# automotive-microcontroller-small-junctio.net
KiCad netlist of a schematic drawn in Altium Designer
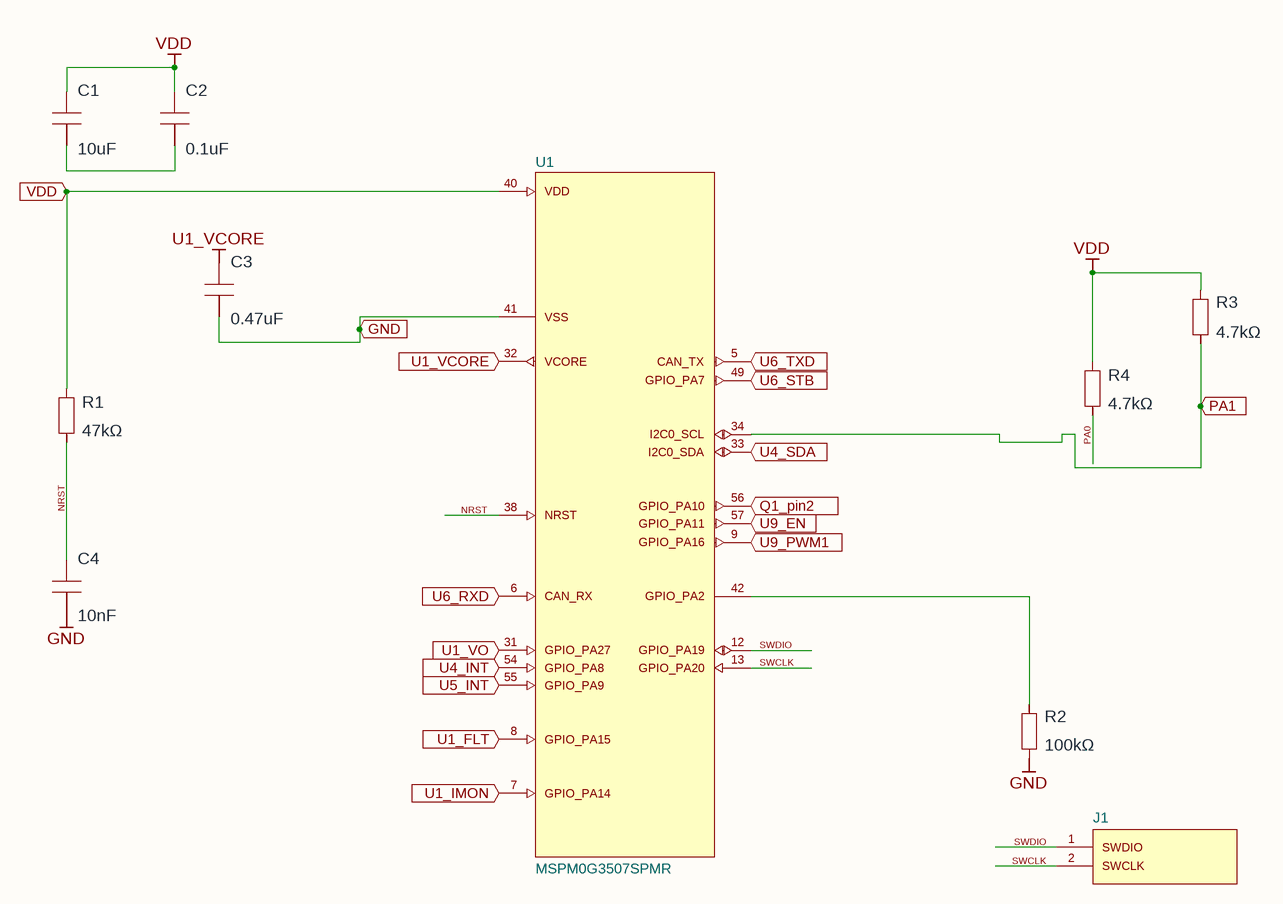
[diagram p0: automotive-microcontroller-small-junctions.SchDoc]

(export (version "E")
  (design (tool "Eeschema 10.0.6"))
  (components
    (comp (ref "C1") (value "10uF") (libsource (lib "altium-import") (part "root_0_capacitor_down_")))
    (comp (ref "C2") (value "0.1uF") (libsource (lib "altium-import") (part "root_0_capacitor_down_")))
    (comp (ref "C3") (value "0.47uF") (libsource (lib "altium-import") (part "root_0_capacitor_down_")))
    (comp (ref "C4") (value "10nF") (libsource (lib "altium-import") (part "root_0_capacitor_down_")))
    (comp (ref "J1") (value "~") (libsource (lib "altium-import") (part "root_0_J1_")))
    (comp (ref "R1") (value "47kΩ") (libsource (lib "altium-import") (part "root_0_boxresistor_up_")))
    (comp (ref "R2") (value "100kΩ") (libsource (lib "altium-import") (part "root_0_boxresistor_down_")))
    (comp (ref "R3") (value "4.7kΩ") (libsource (lib "") (part "root_0_boxresistor_up__1")))
    (comp (ref "R4") (value "4.7kΩ") (libsource (lib "altium-import") (part "root_0_boxresistor_up_")))
    (comp (ref "U1") (value "~") (libsource (lib "altium-import") (part "root_0_U1_")))
  )
  (nets
    (net (code "1") (name "/PA1") (class "Default")
      (node (ref "R3") (pin "1") (pinfunction "anode_1") (pintype "passive"))
      (node (ref "U1") (pin "34") (pinfunction "I2C0_SCL_34") (pintype "passive"))
    )
    (net (code "2") (name "/Q1_pin2") (class "Default")
      (node (ref "U1") (pin "56") (pinfunction "GPIO_PA10_56") (pintype "passive"))
    )
    (net (code "3") (name "/U1_FLT") (class "Default")
      (node (ref "U1") (pin "8") (pinfunction "GPIO_PA15_8") (pintype "passive"))
    )
    (net (code "4") (name "/U1_IMON") (class "Default")
      (node (ref "U1") (pin "7") (pinfunction "GPIO_PA14_7") (pintype "passive"))
    )
    (net (code "5") (name "/U1_VO") (class "Default")
      (node (ref "U1") (pin "31") (pinfunction "GPIO_PA27_31") (pintype "passive"))
    )
    (net (code "6") (name "/U4_INT") (class "Default")
      (node (ref "U1") (pin "54") (pinfunction "GPIO_PA8_54") (pintype "passive"))
    )
    (net (code "7") (name "/U4_SDA") (class "Default")
      (node (ref "U1") (pin "33") (pinfunction "I2C0_SDA_33") (pintype "passive"))
    )
    (net (code "8") (name "/U5_INT") (class "Default")
      (node (ref "U1") (pin "55") (pinfunction "GPIO_PA9_55") (pintype "passive"))
    )
    (net (code "9") (name "/U6_RXD") (class "Default")
      (node (ref "U1") (pin "6") (pinfunction "CAN_RX_6") (pintype "passive"))
    )
    (net (code "10") (name "/U6_STB") (class "Default")
      (node (ref "U1") (pin "49") (pinfunction "GPIO_PA7_49") (pintype "passive"))
    )
    (net (code "11") (name "/U6_TXD") (class "Default")
      (node (ref "U1") (pin "5") (pinfunction "CAN_TX_5") (pintype "passive"))
    )
    (net (code "12") (name "/U9_EN") (class "Default")
      (node (ref "U1") (pin "57") (pinfunction "GPIO_PA11_57") (pintype "passive"))
    )
    (net (code "13") (name "/U9_PWM1") (class "Default")
      (node (ref "U1") (pin "9") (pinfunction "GPIO_PA16_9") (pintype "passive"))
    )
    (net (code "14") (name "GND") (class "Default")
      (node (ref "C3") (pin "2") (pinfunction "cathode_2") (pintype "passive"))
      (node (ref "C4") (pin "2") (pinfunction "cathode_2") (pintype "passive"))
      (node (ref "R2") (pin "2") (pinfunction "cathode_2") (pintype "passive"))
      (node (ref "U1") (pin "41") (pinfunction "VSS_41") (pintype "passive"))
    )
    (net (code "15") (name "Net-(C1-cathode)") (class "Default")
      (node (ref "C1") (pin "2") (pinfunction "cathode_2") (pintype "passive"))
      (node (ref "C2") (pin "2") (pinfunction "cathode_2") (pintype "passive"))
    )
    (net (code "16") (name "Net-(C4-anode)") (class "Default")
      (node (ref "C4") (pin "1") (pinfunction "anode_1") (pintype "passive"))
      (node (ref "R1") (pin "1") (pinfunction "anode_1") (pintype "passive"))
    )
    (net (code "17") (name "Net-(R2-anode)") (class "Default")
      (node (ref "R2") (pin "1") (pinfunction "anode_1") (pintype "passive"))
      (node (ref "U1") (pin "42") (pinfunction "GPIO_PA2_42") (pintype "passive"))
    )
    (net (code "18") (name "U1_VCORE") (class "Default")
      (node (ref "C3") (pin "1") (pinfunction "anode_1") (pintype "passive"))
      (node (ref "U1") (pin "32") (pinfunction "VCORE_32") (pintype "passive"))
    )
    (net (code "19") (name "VDD") (class "Default")
      (node (ref "C1") (pin "1") (pinfunction "anode_1") (pintype "passive"))
      (node (ref "C2") (pin "1") (pinfunction "anode_1") (pintype "passive"))
      (node (ref "R1") (pin "2") (pinfunction "cathode_2") (pintype "passive"))
      (node (ref "R3") (pin "2") (pinfunction "cathode_2") (pintype "passive"))
      (node (ref "R4") (pin "2") (pinfunction "cathode_2") (pintype "passive"))
      (node (ref "U1") (pin "40") (pinfunction "VDD_40") (pintype "passive"))
    )
    (net (code "20") (name "unconnected-(J1-SWCLK-Pad2)") (class "Default")
      (node (ref "J1") (pin "2") (pinfunction "SWCLK_2") (pintype "passive"))
    )
    (net (code "21") (name "unconnected-(J1-SWDIO-Pad1)") (class "Default")
      (node (ref "J1") (pin "1") (pinfunction "SWDIO_1") (pintype "passive"))
    )
    (net (code "22") (name "unconnected-(R4-anode-Pad1)") (class "Default")
      (node (ref "R4") (pin "1") (pinfunction "anode_1") (pintype "passive"))
    )
    (net (code "23") (name "unconnected-(U1-GPIO_PA19-Pad12)") (class "Default")
      (node (ref "U1") (pin "12") (pinfunction "GPIO_PA19_12") (pintype "passive"))
    )
    (net (code "24") (name "unconnected-(U1-GPIO_PA20-Pad13)") (class "Default")
      (node (ref "U1") (pin "13") (pinfunction "GPIO_PA20_13") (pintype "passive"))
    )
    (net (code "25") (name "unconnected-(U1-NRST-Pad38)") (class "Default")
      (node (ref "U1") (pin "38") (pinfunction "NRST_38") (pintype "passive"))
    )
  )
)
